# ELEC327_V3.net
KiCad netlist of a schematic drawn in EAGLE
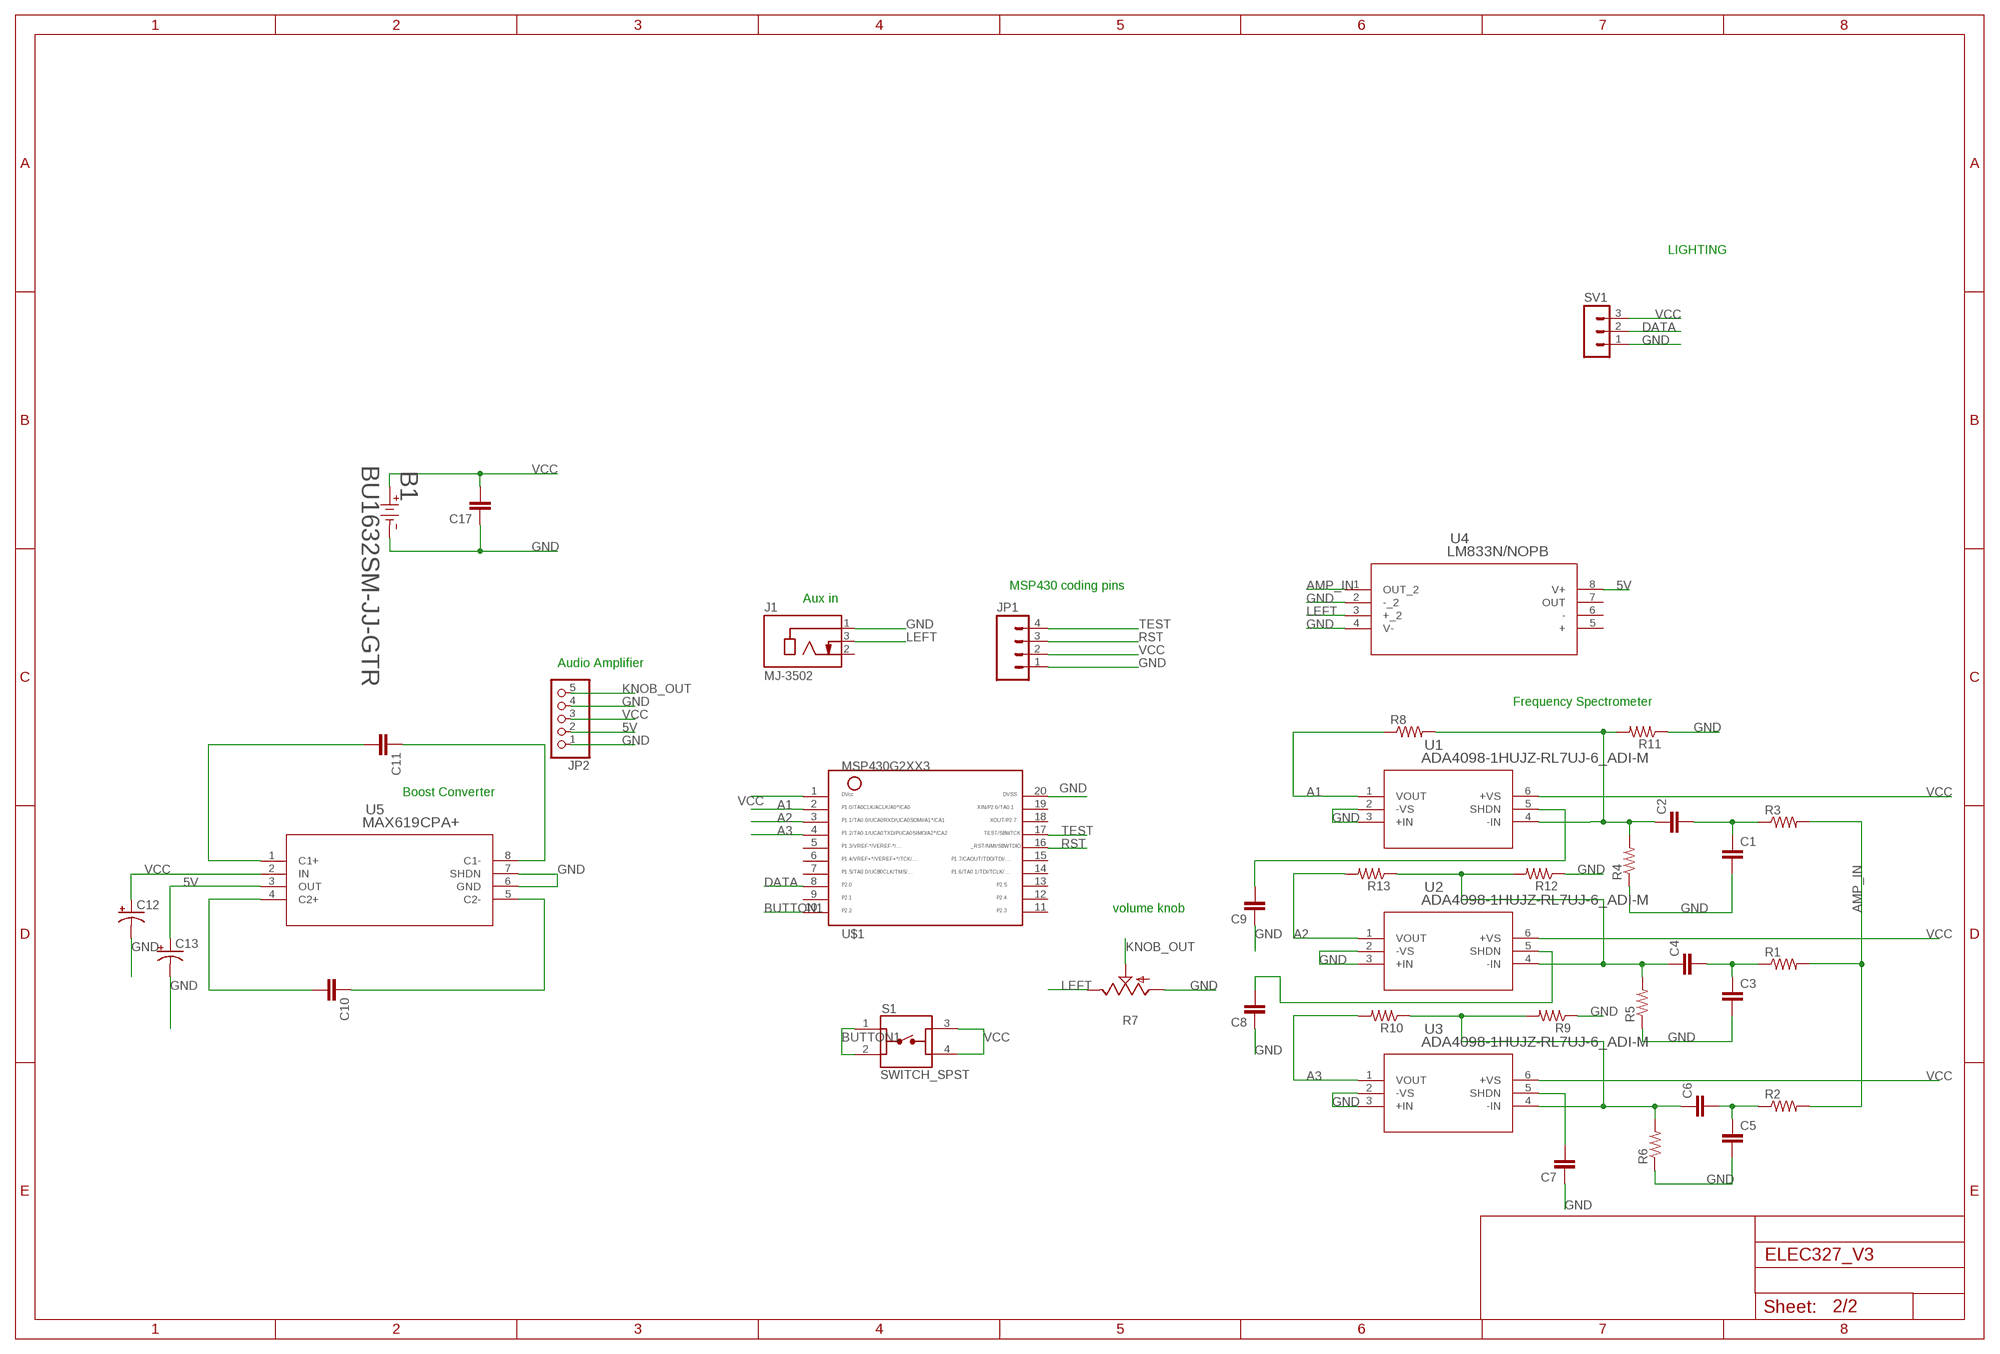
[diagram p0: schematic, sheet 2]

(export (version "E")
  (design (tool "Eeschema 10.0.6"))
  (components
    (comp (ref "B1")
      (value "BU1632SM-JJ-GTR")
      (footprint "eagle-import:BU1632SM-JJ-GTR_MPD")
      (fields (field (name "COPYRIGHT") "Copyright (C) 2023 Ultra Librarian. All rights reserved."))
      (libsource (lib "eagle-import") (part "BU1632SM-JJ-GTR"))
    )
    (comp (ref "C1")
      (value "C-EUC1206")
      (footprint "eagle-import:C1206")
      (libsource (lib "eagle-import") (part "C-EUC1206"))
    )
    (comp (ref "C2")
      (value "C-EUC1206")
      (footprint "eagle-import:C1206")
      (libsource (lib "eagle-import") (part "C-EUC1206"))
    )
    (comp (ref "C3")
      (value "C-EUC1206")
      (footprint "eagle-import:C1206")
      (libsource (lib "eagle-import") (part "C-EUC1206"))
    )
    (comp (ref "C4")
      (value "C-EUC1206")
      (footprint "eagle-import:C1206")
      (libsource (lib "eagle-import") (part "C-EUC1206"))
    )
    (comp (ref "C5")
      (value "C-EUC1206")
      (footprint "eagle-import:C1206")
      (libsource (lib "eagle-import") (part "C-EUC1206"))
    )
    (comp (ref "C6")
      (value "C-EUC1206")
      (footprint "eagle-import:C1206")
      (libsource (lib "eagle-import") (part "C-EUC1206"))
    )
    (comp (ref "C7")
      (value "C-EUC1206")
      (footprint "eagle-import:C1206")
      (libsource (lib "eagle-import") (part "C-EUC1206"))
    )
    (comp (ref "C8")
      (value "C-EUC1206")
      (footprint "eagle-import:C1206")
      (libsource (lib "eagle-import") (part "C-EUC1206"))
    )
    (comp (ref "C9")
      (value "C-EUC1206")
      (footprint "eagle-import:C1206")
      (libsource (lib "eagle-import") (part "C-EUC1206"))
    )
    (comp (ref "C10")
      (value "C-EUC1206")
      (footprint "eagle-import:C1206")
      (libsource (lib "eagle-import") (part "C-EUC1206"))
    )
    (comp (ref "C11")
      (value "C-EUC1206")
      (footprint "eagle-import:C1206")
      (libsource (lib "eagle-import") (part "C-EUC1206"))
    )
    (comp (ref "C12")
      (value "CPOL-USE5-6")
      (footprint "eagle-import:E5-6")
      (libsource (lib "eagle-import") (part "CPOL-USE5-6"))
    )
    (comp (ref "C13")
      (value "CPOL-USE5-6")
      (footprint "eagle-import:E5-6")
      (libsource (lib "eagle-import") (part "CPOL-USE5-6"))
    )
    (comp (ref "C17")
      (value "C-EUC1206")
      (footprint "eagle-import:C1206")
      (libsource (lib "eagle-import") (part "C-EUC1206"))
    )
    (comp (ref "J1")
      (value "MJ-3502")
      (footprint "eagle-import:CUI_MJ-3502")
      (fields (field (name "MANUFACTURER") "CUI INC"))
      (libsource (lib "eagle-import") (part "MJ-3502"))
    )
    (comp (ref "JP1")
      (value "HEADER_1X04LOCK")
      (footprint "eagle-import:1X04_LOCK")
      (libsource (lib "eagle-import") (part "HEADER_1X04LOCK"))
    )
    (comp (ref "JP2")
      (value "PINHD-1X55X2MM")
      (footprint "eagle-import:1_05X2MM")
      (libsource (lib "eagle-import") (part "PINHD-1X55X2MM"))
    )
    (comp (ref "R1")
      (value "R-US_R1206")
      (footprint "eagle-import:R1206")
      (libsource (lib "eagle-import") (part "R-US_R1206"))
    )
    (comp (ref "R2")
      (value "R-US_R1206")
      (footprint "eagle-import:R1206")
      (libsource (lib "eagle-import") (part "R-US_R1206"))
    )
    (comp (ref "R3")
      (value "R-US_R1206")
      (footprint "eagle-import:R1206")
      (libsource (lib "eagle-import") (part "R-US_R1206"))
    )
    (comp (ref "R4")
      (value "R-US_R1206")
      (footprint "eagle-import:R1206")
      (libsource (lib "eagle-import") (part "R-US_R1206"))
    )
    (comp (ref "R5")
      (value "R-US_R1206")
      (footprint "eagle-import:R1206")
      (libsource (lib "eagle-import") (part "R-US_R1206"))
    )
    (comp (ref "R6")
      (value "R-US_R1206")
      (footprint "eagle-import:R1206")
      (libsource (lib "eagle-import") (part "R-US_R1206"))
    )
    (comp (ref "R7")
      (value "TRIM_US-B25X")
      (footprint "eagle-import:B25X")
      (libsource (lib "eagle-import") (part "TRIM_US-B25X"))
    )
    (comp (ref "R8")
      (value "R-US_R1206")
      (footprint "eagle-import:R1206")
      (libsource (lib "eagle-import") (part "R-US_R1206"))
    )
    (comp (ref "R9")
      (value "R-US_R1206")
      (footprint "eagle-import:R1206")
      (libsource (lib "eagle-import") (part "R-US_R1206"))
    )
    (comp (ref "R10")
      (value "R-US_R1206")
      (footprint "eagle-import:R1206")
      (libsource (lib "eagle-import") (part "R-US_R1206"))
    )
    (comp (ref "R11")
      (value "R-US_R1206")
      (footprint "eagle-import:R1206")
      (libsource (lib "eagle-import") (part "R-US_R1206"))
    )
    (comp (ref "R12")
      (value "R-US_R1206")
      (footprint "eagle-import:R1206")
      (libsource (lib "eagle-import") (part "R-US_R1206"))
    )
    (comp (ref "R13")
      (value "R-US_R1206")
      (footprint "eagle-import:R1206")
      (libsource (lib "eagle-import") (part "R-US_R1206"))
    )
    (comp (ref "S1")
      (value "SWITCH_SPST")
      (footprint "eagle-import:SW_1825910-7")
      (fields
        (field (name "COMMENT") "1825910-7")
        (field (name "DIGI-KEY_PART_NUMBER") "450-1804-ND")
        (field (name "MF") "TE Connectivity")
      )
      (libsource (lib "eagle-import") (part "SWITCH_SPST"))
    )
    (comp (ref "SV1")
      (value "MA03-1")
      (footprint "eagle-import:MA03-1")
      (libsource (lib "eagle-import") (part "MA03-1"))
    )
    (comp (ref "U$1")
      (value "MSP430G2XX3TSSOP")
      (footprint "eagle-import:PW20")
      (libsource (lib "eagle-import") (part "MSP430G2XX3TSSOP"))
    )
    (comp (ref "U1")
      (value "ADA4098-1HUJZ-RL7UJ-6_ADI-M")
      (footprint "eagle-import:UJ-6_ADI-M")
      (fields
        (field (name "MANUFACTURER_PART_NUMBER") "ADA4098-1HUJZ-RL7")
        (field (name "COPYRIGHT") "Copyright (C) 2023 Ultra Librarian. All rights reserved.")
      )
      (libsource (lib "eagle-import") (part "ADA4098-1HUJZ-RL7UJ-6_ADI-M"))
    )
    (comp (ref "U2")
      (value "ADA4098-1HUJZ-RL7UJ-6_ADI-M")
      (footprint "eagle-import:UJ-6_ADI-M")
      (fields
        (field (name "MANUFACTURER_PART_NUMBER") "ADA4098-1HUJZ-RL7")
        (field (name "COPYRIGHT") "Copyright (C) 2023 Ultra Librarian. All rights reserved.")
      )
      (libsource (lib "eagle-import") (part "ADA4098-1HUJZ-RL7UJ-6_ADI-M"))
    )
    (comp (ref "U3")
      (value "ADA4098-1HUJZ-RL7UJ-6_ADI-M")
      (footprint "eagle-import:UJ-6_ADI-M")
      (fields
        (field (name "MANUFACTURER_PART_NUMBER") "ADA4098-1HUJZ-RL7")
        (field (name "COPYRIGHT") "Copyright (C) 2023 Ultra Librarian. All rights reserved.")
      )
      (libsource (lib "eagle-import") (part "ADA4098-1HUJZ-RL7UJ-6_ADI-M"))
    )
    (comp (ref "U4")
      (value "LM833N/NOPB")
      (footprint "eagle-import:N08E_TEX")
      (fields (field (name "COPYRIGHT") "Copyright (C) 2023 Ultra Librarian. All rights reserved."))
      (libsource (lib "eagle-import") (part "LM833N/NOPB"))
    )
    (comp (ref "U5")
      (value "MAX619CPA+")
      (footprint "eagle-import:21-0043D_8_MXM")
      (fields (field (name "COPYRIGHT") "Copyright (C) 2023 Ultra Librarian. All rights reserved."))
      (libsource (lib "eagle-import") (part "MAX619CPA+"))
    )
  )
  (nets
    (net (code "1") (name "5V") (class "Default")
      (node (ref "C13") (pin "+") (pinfunction "+_+") (pintype "passive"))
      (node (ref "JP2") (pin "2") (pinfunction "2_2") (pintype "passive"))
      (node (ref "U4") (pin "8") (pinfunction "V+_8") (pintype "passive"))
      (node (ref "U5") (pin "3") (pinfunction "OUT_3") (pintype "output"))
    )
    (net (code "2") (name "A1") (class "Default")
      (node (ref "R8") (pin "1") (pinfunction "1_1") (pintype "passive"))
      (node (ref "U$1") (pin "2") (pinfunction "2_2") (pintype "bidirectional"))
      (node (ref "U1") (pin "1") (pinfunction "VOUT_1") (pintype "output"))
    )
    (net (code "3") (name "A2") (class "Default")
      (node (ref "R13") (pin "2") (pinfunction "2_2") (pintype "passive"))
      (node (ref "U$1") (pin "3") (pinfunction "3_3") (pintype "bidirectional"))
      (node (ref "U2") (pin "1") (pinfunction "VOUT_1") (pintype "output"))
    )
    (net (code "4") (name "A3") (class "Default")
      (node (ref "R10") (pin "2") (pinfunction "2_2") (pintype "passive"))
      (node (ref "U$1") (pin "4") (pinfunction "4_4") (pintype "bidirectional"))
      (node (ref "U3") (pin "1") (pinfunction "VOUT_1") (pintype "output"))
    )
    (net (code "5") (name "AMP_IN") (class "Default")
      (node (ref "R1") (pin "2") (pinfunction "2_2") (pintype "passive"))
      (node (ref "R2") (pin "2") (pinfunction "2_2") (pintype "passive"))
      (node (ref "R3") (pin "2") (pinfunction "2_2") (pintype "passive"))
      (node (ref "U4") (pin "1") (pinfunction "OUT_2_1") (pintype "passive"))
    )
    (net (code "6") (name "BUTTON1") (class "Default")
      (node (ref "S1") (pin "1") (pinfunction "1_1") (pintype "passive"))
      (node (ref "S1") (pin "2") (pinfunction "2_2") (pintype "passive"))
      (node (ref "U$1") (pin "10") (pinfunction "10_10") (pintype "bidirectional"))
    )
    (net (code "7") (name "DATA") (class "Default")
      (node (ref "SV1") (pin "2") (pinfunction "2_2") (pintype "passive"))
      (node (ref "U$1") (pin "8") (pinfunction "8_8") (pintype "bidirectional"))
    )
    (net (code "8") (name "GND") (class "Default")
      (node (ref "B1") (pin "2") (pinfunction "2_2") (pintype "passive"))
      (node (ref "C1") (pin "2") (pinfunction "2_2") (pintype "passive"))
      (node (ref "C12") (pin "-") (pinfunction "-_-") (pintype "passive"))
      (node (ref "C13") (pin "-") (pinfunction "-_-") (pintype "passive"))
      (node (ref "C17") (pin "1") (pinfunction "1_1") (pintype "passive"))
      (node (ref "C3") (pin "2") (pinfunction "2_2") (pintype "passive"))
      (node (ref "C5") (pin "2") (pinfunction "2_2") (pintype "passive"))
      (node (ref "C7") (pin "1") (pinfunction "1_1") (pintype "passive"))
      (node (ref "C8") (pin "1") (pinfunction "1_1") (pintype "passive"))
      (node (ref "C9") (pin "1") (pinfunction "1_1") (pintype "passive"))
      (node (ref "J1") (pin "1") (pinfunction "1_1") (pintype "passive"))
      (node (ref "JP1") (pin "1") (pinfunction "1_1") (pintype "passive"))
      (node (ref "JP2") (pin "1") (pinfunction "1_1") (pintype "passive"))
      (node (ref "JP2") (pin "4") (pinfunction "4_4") (pintype "passive"))
      (node (ref "R11") (pin "1") (pinfunction "1_1") (pintype "passive"))
      (node (ref "R12") (pin "1") (pinfunction "1_1") (pintype "passive"))
      (node (ref "R4") (pin "1") (pinfunction "1_1") (pintype "passive"))
      (node (ref "R5") (pin "1") (pinfunction "1_1") (pintype "passive"))
      (node (ref "R6") (pin "1") (pinfunction "1_1") (pintype "passive"))
      (node (ref "R7") (pin "A") (pinfunction "A_A") (pintype "passive"))
      (node (ref "R9") (pin "1") (pinfunction "1_1") (pintype "passive"))
      (node (ref "SV1") (pin "1") (pinfunction "1_1") (pintype "passive"))
      (node (ref "U$1") (pin "20") (pinfunction "20_20") (pintype "bidirectional"))
      (node (ref "U1") (pin "2") (pinfunction "-VS_2") (pintype "power_in"))
      (node (ref "U1") (pin "3") (pinfunction "+IN_3") (pintype "input"))
      (node (ref "U2") (pin "2") (pinfunction "-VS_2") (pintype "power_in"))
      (node (ref "U2") (pin "3") (pinfunction "+IN_3") (pintype "input"))
      (node (ref "U3") (pin "2") (pinfunction "-VS_2") (pintype "power_in"))
      (node (ref "U3") (pin "3") (pinfunction "+IN_3") (pintype "input"))
      (node (ref "U4") (pin "2") (pinfunction "-_2_2") (pintype "passive"))
      (node (ref "U4") (pin "4") (pinfunction "V-_4") (pintype "passive"))
      (node (ref "U5") (pin "6") (pinfunction "GND_6") (pintype "passive"))
      (node (ref "U5") (pin "7") (pinfunction "SHDN_7") (pintype "input"))
    )
    (net (code "9") (name "KNOB_OUT") (class "Default")
      (node (ref "JP2") (pin "5") (pinfunction "5_5") (pintype "passive"))
      (node (ref "R7") (pin "S") (pinfunction "S_S") (pintype "passive"))
    )
    (net (code "10") (name "LEFT") (class "Default")
      (node (ref "J1") (pin "3") (pinfunction "3_3") (pintype "passive"))
      (node (ref "R7") (pin "E") (pinfunction "E_E") (pintype "passive"))
      (node (ref "U4") (pin "3") (pinfunction "+_2_3") (pintype "passive"))
    )
    (net (code "11") (name "Net-(C1-Pad1)") (class "Default")
      (node (ref "C1") (pin "1") (pinfunction "1_1") (pintype "passive"))
      (node (ref "C2") (pin "2") (pinfunction "2_2") (pintype "passive"))
      (node (ref "R3") (pin "1") (pinfunction "1_1") (pintype "passive"))
    )
    (net (code "12") (name "Net-(C3-Pad1)") (class "Default")
      (node (ref "C3") (pin "1") (pinfunction "1_1") (pintype "passive"))
      (node (ref "C4") (pin "2") (pinfunction "2_2") (pintype "passive"))
      (node (ref "R1") (pin "1") (pinfunction "1_1") (pintype "passive"))
    )
    (net (code "13") (name "Net-(C5-Pad1)") (class "Default")
      (node (ref "C5") (pin "1") (pinfunction "1_1") (pintype "passive"))
      (node (ref "C6") (pin "2") (pinfunction "2_2") (pintype "passive"))
      (node (ref "R2") (pin "1") (pinfunction "1_1") (pintype "passive"))
    )
    (net (code "14") (name "Net-(U1--IN)") (class "Default")
      (node (ref "C2") (pin "1") (pinfunction "1_1") (pintype "passive"))
      (node (ref "R11") (pin "2") (pinfunction "2_2") (pintype "passive"))
      (node (ref "R4") (pin "2") (pinfunction "2_2") (pintype "passive"))
      (node (ref "R8") (pin "2") (pinfunction "2_2") (pintype "passive"))
      (node (ref "U1") (pin "4") (pinfunction "-IN_4") (pintype "input"))
    )
    (net (code "15") (name "Net-(U1-SHDN)") (class "Default")
      (node (ref "C9") (pin "2") (pinfunction "2_2") (pintype "passive"))
      (node (ref "U1") (pin "5") (pinfunction "SHDN_5") (pintype "input"))
    )
    (net (code "16") (name "Net-(U2--IN)") (class "Default")
      (node (ref "C4") (pin "1") (pinfunction "1_1") (pintype "passive"))
      (node (ref "R12") (pin "2") (pinfunction "2_2") (pintype "passive"))
      (node (ref "R13") (pin "1") (pinfunction "1_1") (pintype "passive"))
      (node (ref "R5") (pin "2") (pinfunction "2_2") (pintype "passive"))
      (node (ref "U2") (pin "4") (pinfunction "-IN_4") (pintype "input"))
    )
    (net (code "17") (name "Net-(U2-SHDN)") (class "Default")
      (node (ref "C8") (pin "2") (pinfunction "2_2") (pintype "passive"))
      (node (ref "U2") (pin "5") (pinfunction "SHDN_5") (pintype "input"))
    )
    (net (code "18") (name "Net-(U3--IN)") (class "Default")
      (node (ref "C6") (pin "1") (pinfunction "1_1") (pintype "passive"))
      (node (ref "R10") (pin "1") (pinfunction "1_1") (pintype "passive"))
      (node (ref "R6") (pin "2") (pinfunction "2_2") (pintype "passive"))
      (node (ref "R9") (pin "2") (pinfunction "2_2") (pintype "passive"))
      (node (ref "U3") (pin "4") (pinfunction "-IN_4") (pintype "input"))
    )
    (net (code "19") (name "Net-(U3-SHDN)") (class "Default")
      (node (ref "C7") (pin "2") (pinfunction "2_2") (pintype "passive"))
      (node (ref "U3") (pin "5") (pinfunction "SHDN_5") (pintype "input"))
    )
    (net (code "20") (name "Net-(U5-C1+)") (class "Default")
      (node (ref "C11") (pin "2") (pinfunction "2_2") (pintype "passive"))
      (node (ref "U5") (pin "1") (pinfunction "C1+_1") (pintype "passive"))
    )
    (net (code "21") (name "Net-(U5-C1-)") (class "Default")
      (node (ref "C11") (pin "1") (pinfunction "1_1") (pintype "passive"))
      (node (ref "U5") (pin "8") (pinfunction "C1-_8") (pintype "passive"))
    )
    (net (code "22") (name "Net-(U5-C2+)") (class "Default")
      (node (ref "C10") (pin "2") (pinfunction "2_2") (pintype "passive"))
      (node (ref "U5") (pin "4") (pinfunction "C2+_4") (pintype "passive"))
    )
    (net (code "23") (name "Net-(U5-C2-)") (class "Default")
      (node (ref "C10") (pin "1") (pinfunction "1_1") (pintype "passive"))
      (node (ref "U5") (pin "5") (pinfunction "C2-_5") (pintype "passive"))
    )
    (net (code "24") (name "RST") (class "Default")
      (node (ref "JP1") (pin "3") (pinfunction "3_3") (pintype "passive"))
      (node (ref "U$1") (pin "16") (pinfunction "16_16") (pintype "bidirectional"))
    )
    (net (code "25") (name "TEST") (class "Default")
      (node (ref "JP1") (pin "4") (pinfunction "4_4") (pintype "passive"))
      (node (ref "U$1") (pin "17") (pinfunction "17_17") (pintype "bidirectional"))
    )
    (net (code "26") (name "VCC") (class "Default")
      (node (ref "B1") (pin "1") (pinfunction "1_1") (pintype "passive"))
      (node (ref "C12") (pin "+") (pinfunction "+_+") (pintype "passive"))
      (node (ref "C17") (pin "2") (pinfunction "2_2") (pintype "passive"))
      (node (ref "JP1") (pin "2") (pinfunction "2_2") (pintype "passive"))
      (node (ref "JP2") (pin "3") (pinfunction "3_3") (pintype "passive"))
      (node (ref "S1") (pin "3") (pinfunction "3_3") (pintype "passive"))
      (node (ref "S1") (pin "4") (pinfunction "4_4") (pintype "passive"))
      (node (ref "SV1") (pin "3") (pinfunction "3_3") (pintype "passive"))
      (node (ref "U$1") (pin "1") (pinfunction "1_1") (pintype "bidirectional"))
      (node (ref "U1") (pin "6") (pinfunction "+VS_6") (pintype "power_in"))
      (node (ref "U2") (pin "6") (pinfunction "+VS_6") (pintype "power_in"))
      (node (ref "U3") (pin "6") (pinfunction "+VS_6") (pintype "power_in"))
      (node (ref "U5") (pin "2") (pinfunction "IN_2") (pintype "input"))
    )
    (net (code "27") (name "unconnected-(J1-Pad2)") (class "Default")
      (node (ref "J1") (pin "2") (pinfunction "2_2") (pintype "passive"))
    )
    (net (code "28") (name "unconnected-(U$1-Pad5)") (class "Default")
      (node (ref "U$1") (pin "5") (pinfunction "5_5") (pintype "bidirectional"))
    )
    (net (code "29") (name "unconnected-(U$1-Pad6)") (class "Default")
      (node (ref "U$1") (pin "6") (pinfunction "6_6") (pintype "bidirectional"))
    )
    (net (code "30") (name "unconnected-(U$1-Pad7)") (class "Default")
      (node (ref "U$1") (pin "7") (pinfunction "7_7") (pintype "bidirectional"))
    )
    (net (code "31") (name "unconnected-(U$1-Pad9)") (class "Default")
      (node (ref "U$1") (pin "9") (pinfunction "9_9") (pintype "bidirectional"))
    )
    (net (code "32") (name "unconnected-(U$1-Pad11)") (class "Default")
      (node (ref "U$1") (pin "11") (pinfunction "11_11") (pintype "bidirectional"))
    )
    (net (code "33") (name "unconnected-(U$1-Pad12)") (class "Default")
      (node (ref "U$1") (pin "12") (pinfunction "12_12") (pintype "bidirectional"))
    )
    (net (code "34") (name "unconnected-(U$1-Pad13)") (class "Default")
      (node (ref "U$1") (pin "13") (pinfunction "13_13") (pintype "bidirectional"))
    )
    (net (code "35") (name "unconnected-(U$1-Pad14)") (class "Default")
      (node (ref "U$1") (pin "14") (pinfunction "14_14") (pintype "bidirectional"))
    )
    (net (code "36") (name "unconnected-(U$1-Pad15)") (class "Default")
      (node (ref "U$1") (pin "15") (pinfunction "15_15") (pintype "bidirectional"))
    )
    (net (code "37") (name "unconnected-(U$1-Pad18)") (class "Default")
      (node (ref "U$1") (pin "18") (pinfunction "18_18") (pintype "bidirectional"))
    )
    (net (code "38") (name "unconnected-(U$1-Pad19)") (class "Default")
      (node (ref "U$1") (pin "19") (pinfunction "19_19") (pintype "bidirectional"))
    )
    (net (code "39") (name "unconnected-(U4-+-Pad5)") (class "Default")
      (node (ref "U4") (pin "5") (pinfunction "+_5") (pintype "passive"))
    )
    (net (code "40") (name "unconnected-(U4---Pad6)") (class "Default")
      (node (ref "U4") (pin "6") (pinfunction "-_6") (pintype "passive"))
    )
    (net (code "41") (name "unconnected-(U4-OUT-Pad7)") (class "Default")
      (node (ref "U4") (pin "7") (pinfunction "OUT_7") (pintype "passive"))
    )
  )
)
